# Fri3D_2026_ESP32.net
KiCad netlist of a schematic drawn in Altium Designer
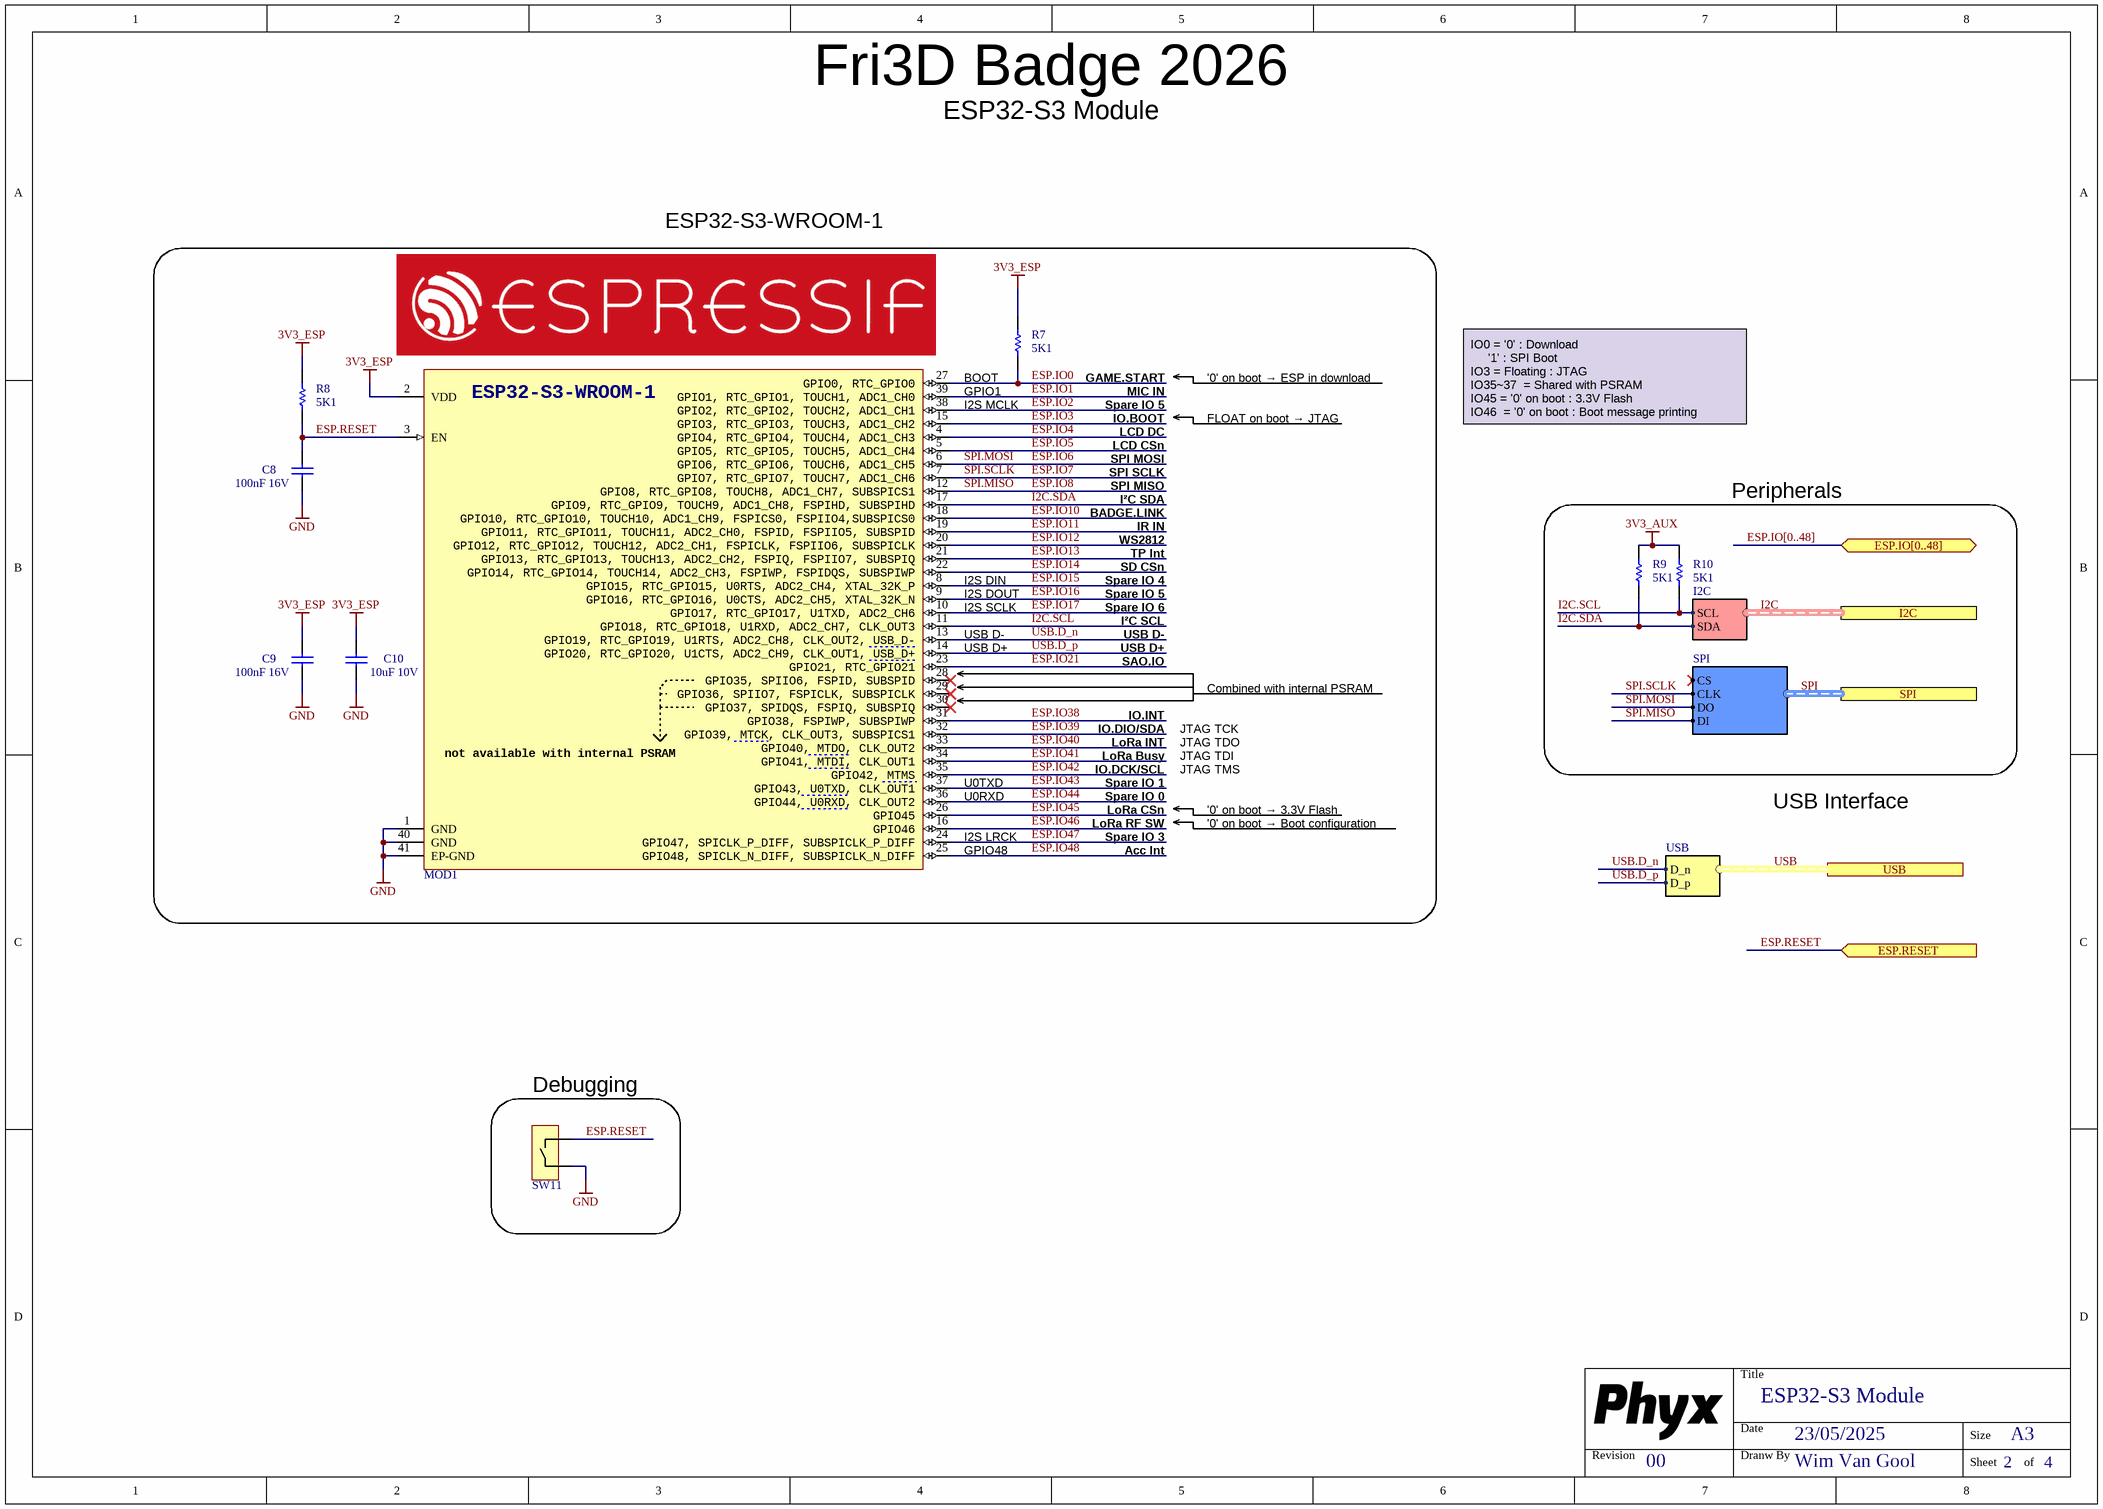
[diagram p0: Fri3D_2026_ESP32.SchDoc]

(export (version "E")
  (design (tool "Eeschema 10.0.6"))
  (components
    (comp (ref "C8")
      (value "100nF 16V")
      (footprint "C0603_N")
      (description "Capacitor Ceramic")
      (libsource (lib "Phyx_Components") (part "CAP_CERAMIC"))
    )
    (comp (ref "C9")
      (value "100nF 16V")
      (footprint "C0603_N")
      (description "Capacitor Ceramic")
      (libsource (lib "Phyx_Components") (part "CAP_CERAMIC"))
    )
    (comp (ref "C10")
      (value "10uF 10V")
      (footprint "C0805_N")
      (description "Capacitor Ceramic")
      (libsource (lib "Phyx_Components") (part "CAP_CERAMIC"))
    )
    (comp (ref "MOD1")
      (value "ESP32-S3 based WROOM-1 16MB Flash, 8MB PSRAM")
      (footprint "ESP-ESP32-S3-WROOM-1")
      (description "WiFi # MOD ESP32-S3-WROOM-1")
      (libsource (lib "Phyx_Components") (part "ESP-ESP32-S3-WROOM-1"))
    )
    (comp (ref "R7")
      (value "5K1")
      (footprint "R0603_N")
      (libsource (lib "Phyx_Components") (part "RESISTOR"))
    )
    (comp (ref "R8")
      (value "5K1")
      (footprint "R0603_N")
      (libsource (lib "Phyx_Components") (part "RESISTOR"))
    )
    (comp (ref "R9")
      (value "5K1")
      (footprint "R0603_N")
      (libsource (lib "Phyx_Components") (part "RESISTOR"))
    )
    (comp (ref "R10")
      (value "5K1")
      (footprint "R0603_N")
      (libsource (lib "Phyx_Components") (part "RESISTOR"))
    )
    (comp (ref "SW11")
      (value "4.5x4.5mm tact SMD H3,8mm")
      (footprint "WE_430181038816")
      (libsource (lib "Phyx_Components") (part "SW_TACT"))
    )
  )
  (nets
    (net (code "24") (name "/ESP.IO0") (class "Default")
      (node (ref "MOD1") (pin "27") (pinfunction "GPIO0,_RTC_GPIO0_27") (pintype "bidirectional"))
      (node (ref "R7") (pin "2") (pinfunction "2_2") (pintype "passive"))
    )
    (net (code "25") (name "/ESP.IO1") (class "Default")
      (node (ref "MOD1") (pin "39") (pinfunction "GPIO1,_RTC_GPIO1,_TOUCH1,_ADC1_CH0_39") (pintype "bidirectional"))
    )
    (net (code "26") (name "/ESP.IO2") (class "Default")
      (node (ref "MOD1") (pin "38") (pinfunction "GPIO2,_RTC_GPIO2,_TOUCH2,_ADC1_CH1_38") (pintype "bidirectional"))
    )
    (net (code "27") (name "/ESP.IO3") (class "Default")
      (node (ref "MOD1") (pin "15") (pinfunction "GPIO3,_RTC_GPIO3,_TOUCH3,_ADC1_CH2_15") (pintype "bidirectional"))
    )
    (net (code "28") (name "/ESP.IO4") (class "Default")
      (node (ref "MOD1") (pin "4") (pinfunction "GPIO4,_RTC_GPIO4,_TOUCH4,_ADC1_CH3_4") (pintype "bidirectional"))
    )
    (net (code "29") (name "/ESP.IO5") (class "Default")
      (node (ref "MOD1") (pin "5") (pinfunction "GPIO5,_RTC_GPIO5,_TOUCH5,_ADC1_CH4_5") (pintype "bidirectional"))
    )
    (net (code "30") (name "/ESP.IO6") (class "Default")
      (node (ref "MOD1") (pin "6") (pinfunction "GPIO6,_RTC_GPIO6,_TOUCH6,_ADC1_CH5_6") (pintype "bidirectional"))
    )
    (net (code "31") (name "/ESP.IO7") (class "Default")
      (node (ref "MOD1") (pin "7") (pinfunction "GPIO7,_RTC_GPIO7,_TOUCH7,_ADC1_CH6_7") (pintype "bidirectional"))
    )
    (net (code "32") (name "/ESP.IO8") (class "Default")
      (node (ref "MOD1") (pin "12") (pinfunction "GPIO8,_RTC_GPIO8,_TOUCH8,_ADC1_CH7,_SUBSPICS1_12") (pintype "bidirectional"))
    )
    (net (code "33") (name "/ESP.IO10") (class "Default")
      (node (ref "MOD1") (pin "18") (pinfunction "GPIO10,_RTC_GPIO10,_TOUCH10,_ADC1_CH9,_FSPICS0,_FSPIIO4,SUBSPICS0_18") (pintype "bidirectional"))
    )
    (net (code "34") (name "/ESP.IO11") (class "Default")
      (node (ref "MOD1") (pin "19") (pinfunction "GPIO11,_RTC_GPIO11,_TOUCH11,_ADC2_CH0,_FSPID,_FSPIIO5,_SUBSPID_19") (pintype "bidirectional"))
    )
    (net (code "35") (name "/ESP.IO12") (class "Default")
      (node (ref "MOD1") (pin "20") (pinfunction "GPIO12,_RTC_GPIO12,_TOUCH12,_ADC2_CH1,_FSPICLK,_FSPIIO6,_SUBSPICLK_20") (pintype "bidirectional"))
    )
    (net (code "36") (name "/ESP.IO13") (class "Default")
      (node (ref "MOD1") (pin "21") (pinfunction "GPIO13,_RTC_GPIO13,_TOUCH13,_ADC2_CH2,_FSPIQ,_FSPIIO7,_SUBSPIQ_21") (pintype "bidirectional"))
    )
    (net (code "37") (name "/ESP.IO14") (class "Default")
      (node (ref "MOD1") (pin "22") (pinfunction "GPIO14,_RTC_GPIO14,_TOUCH14,_ADC2_CH3,_FSPIWP,_FSPIDQS,_SUBSPIWP_22") (pintype "bidirectional"))
    )
    (net (code "38") (name "/ESP.IO15") (class "Default")
      (node (ref "MOD1") (pin "8") (pinfunction "GPIO15,_RTC_GPIO15,_U0RTS,_ADC2_CH4,_XTAL_32K_P_8") (pintype "bidirectional"))
    )
    (net (code "39") (name "/ESP.IO16") (class "Default")
      (node (ref "MOD1") (pin "9") (pinfunction "GPIO16,_RTC_GPIO16,_U0CTS,_ADC2_CH5,_XTAL_32K_N_9") (pintype "bidirectional"))
    )
    (net (code "40") (name "/ESP.IO17") (class "Default")
      (node (ref "MOD1") (pin "10") (pinfunction "GPIO17,_RTC_GPIO17,_U1TXD,_ADC2_CH6_10") (pintype "bidirectional"))
    )
    (net (code "41") (name "/ESP.IO21") (class "Default")
      (node (ref "MOD1") (pin "23") (pinfunction "GPIO21,_RTC_GPIO21_23") (pintype "bidirectional"))
    )
    (net (code "42") (name "/ESP.IO38") (class "Default")
      (node (ref "MOD1") (pin "31") (pinfunction "GPIO38,_FSPIWP,_SUBSPIWP_31") (pintype "bidirectional"))
    )
    (net (code "43") (name "/ESP.IO39") (class "Default")
      (node (ref "MOD1") (pin "32") (pinfunction "GPIO39,_MTCK,_CLK_OUT3,_SUBSPICS1_32") (pintype "bidirectional"))
    )
    (net (code "44") (name "/ESP.IO40") (class "Default")
      (node (ref "MOD1") (pin "33") (pinfunction "GPIO40,_MTDO,_CLK_OUT2_33") (pintype "bidirectional"))
    )
    (net (code "45") (name "/ESP.IO41") (class "Default")
      (node (ref "MOD1") (pin "34") (pinfunction "GPIO41,_MTDI,_CLK_OUT1_34") (pintype "bidirectional"))
    )
    (net (code "46") (name "/ESP.IO42") (class "Default")
      (node (ref "MOD1") (pin "35") (pinfunction "GPIO42,_MTMS_35") (pintype "bidirectional"))
    )
    (net (code "47") (name "/ESP.IO43") (class "Default")
      (node (ref "MOD1") (pin "37") (pinfunction "GPIO43,_U0TXD,_CLK_OUT1_37") (pintype "bidirectional"))
    )
    (net (code "48") (name "/ESP.IO44") (class "Default")
      (node (ref "MOD1") (pin "36") (pinfunction "GPIO44,_U0RXD,_CLK_OUT2_36") (pintype "bidirectional"))
    )
    (net (code "49") (name "/ESP.IO45") (class "Default")
      (node (ref "MOD1") (pin "26") (pinfunction "GPIO45_26") (pintype "bidirectional"))
    )
    (net (code "50") (name "/ESP.IO46") (class "Default")
      (node (ref "MOD1") (pin "16") (pinfunction "GPIO46_16") (pintype "bidirectional"))
    )
    (net (code "51") (name "/ESP.IO47") (class "Default")
      (node (ref "MOD1") (pin "24") (pinfunction "GPIO47,_SPICLK_P_DIFF,_SUBSPICLK_P_DIFF_24") (pintype "bidirectional"))
    )
    (net (code "52") (name "/ESP.IO48") (class "Default")
      (node (ref "MOD1") (pin "25") (pinfunction "GPIO48,_SPICLK_N_DIFF,_SUBSPICLK_N_DIFF_25") (pintype "bidirectional"))
    )
    (net (code "54") (name "/ESP.RESET") (class "Default")
      (node (ref "C8") (pin "1") (pinfunction "1_1") (pintype "passive"))
      (node (ref "MOD1") (pin "3") (pinfunction "EN_3") (pintype "input"))
      (node (ref "R8") (pin "2") (pinfunction "2_2") (pintype "passive"))
      (node (ref "SW11") (pin "1") (pinfunction "1_1") (pintype "passive"))
    )
    (net (code "55") (name "/I2C.SCL") (class "Default")
      (node (ref "MOD1") (pin "11") (pinfunction "GPIO18,_RTC_GPIO18,_U1RXD,_ADC2_CH7,_CLK_OUT3_11") (pintype "bidirectional"))
      (node (ref "R10") (pin "2") (pinfunction "2_2") (pintype "passive"))
    )
    (net (code "56") (name "/I2C.SDA") (class "Default")
      (node (ref "MOD1") (pin "17") (pinfunction "GPIO9,_RTC_GPIO9,_TOUCH9,_ADC1_CH8,_FSPIHD,_SUBSPIHD_17") (pintype "bidirectional"))
      (node (ref "R9") (pin "2") (pinfunction "2_2") (pintype "passive"))
    )
    (net (code "59") (name "/USB.D_n") (class "Default")
      (node (ref "MOD1") (pin "13") (pinfunction "GPIO19,_RTC_GPIO19,_U1RTS,_ADC2_CH8,_CLK_OUT2,_USB_D-_13") (pintype "bidirectional"))
    )
    (net (code "60") (name "/USB.D_p") (class "Default")
      (node (ref "MOD1") (pin "14") (pinfunction "GPIO20,_RTC_GPIO20,_U1CTS,_ADC2_CH9,_CLK_OUT1,_USB_D+_14") (pintype "bidirectional"))
    )
    (net (code "62") (name "3V3_AUX") (class "Default")
      (node (ref "R10") (pin "1") (pinfunction "1_1") (pintype "passive"))
      (node (ref "R9") (pin "1") (pinfunction "1_1") (pintype "passive"))
    )
    (net (code "63") (name "3V3_ESP") (class "Default")
      (node (ref "C10") (pin "1") (pinfunction "1_1") (pintype "passive"))
      (node (ref "C9") (pin "1") (pinfunction "1_1") (pintype "passive"))
      (node (ref "MOD1") (pin "2") (pinfunction "VDD_2") (pintype "power_in"))
      (node (ref "R7") (pin "1") (pinfunction "1_1") (pintype "passive"))
      (node (ref "R8") (pin "1") (pinfunction "1_1") (pintype "passive"))
    )
    (net (code "64") (name "GND") (class "Default")
      (node (ref "C10") (pin "2") (pinfunction "2_2") (pintype "passive"))
      (node (ref "C8") (pin "2") (pinfunction "2_2") (pintype "passive"))
      (node (ref "C9") (pin "2") (pinfunction "2_2") (pintype "passive"))
      (node (ref "MOD1") (pin "1") (pinfunction "GND_1") (pintype "power_in"))
      (node (ref "MOD1") (pin "40") (pinfunction "GND_40") (pintype "power_in"))
      (node (ref "MOD1") (pin "41") (pinfunction "EP-GND_41") (pintype "power_in"))
      (node (ref "SW11") (pin "2") (pinfunction "2_2") (pintype "passive"))
    )
    (net (code "65") (name "unconnected-(MOD1-GPIO35,_SPIIO6,_FSPID,_SUBSPID-Pad28)") (class "Default")
      (node (ref "MOD1") (pin "28") (pinfunction "GPIO35,_SPIIO6,_FSPID,_SUBSPID_28") (pintype "bidirectional+no_connect"))
    )
    (net (code "66") (name "unconnected-(MOD1-GPIO36,_SPIIO7,_FSPICLK,_SUBSPICLK-Pad29)") (class "Default")
      (node (ref "MOD1") (pin "29") (pinfunction "GPIO36,_SPIIO7,_FSPICLK,_SUBSPICLK_29") (pintype "bidirectional+no_connect"))
    )
    (net (code "67") (name "unconnected-(MOD1-GPIO37,_SPIDQS,_FSPIQ,_SUBSPIQ-Pad30)") (class "Default")
      (node (ref "MOD1") (pin "30") (pinfunction "GPIO37,_SPIDQS,_FSPIQ,_SUBSPIQ_30") (pintype "bidirectional+no_connect"))
    )
  )
)
